# pic18f2550usbhdiio.net
KiCad netlist of a schematic drawn in EAGLE
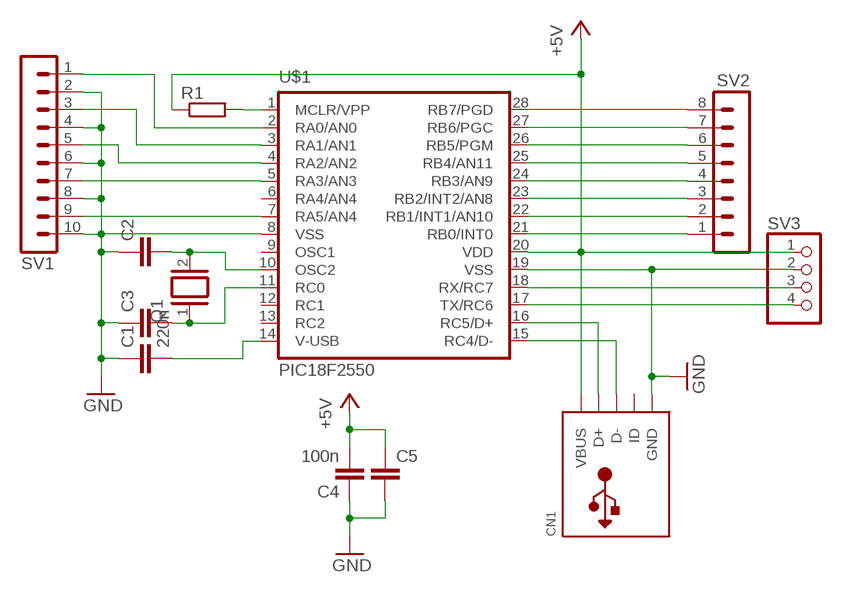
[diagram p0: schematic, sheet 1]

(export (version "E")
  (design (tool "Eeschema 10.0.6"))
  (components
    (comp (ref "C1")
      (value "220n")
      (footprint "eagle-import:C025-025X050")
      (libsource (lib "eagle-import") (part "C-EU025-025X050"))
    )
    (comp (ref "C2")
      (value "C-EU025-025X050")
      (footprint "eagle-import:C025-025X050")
      (libsource (lib "eagle-import") (part "C-EU025-025X050"))
    )
    (comp (ref "C3")
      (value "C-EU025-025X050")
      (footprint "eagle-import:C025-025X050")
      (libsource (lib "eagle-import") (part "C-EU025-025X050"))
    )
    (comp (ref "C4")
      (value "100n")
      (footprint "eagle-import:C025-025X050")
      (libsource (lib "eagle-import") (part "C-EU025-025X050"))
    )
    (comp (ref "C5")
      (value "C-EUC0805K")
      (footprint "eagle-import:C0805K")
      (libsource (lib "eagle-import") (part "C-EUC0805K"))
    )
    (comp (ref "CN1")
      (value "USBMOLEX")
      (footprint "eagle-import:USB-MINIB-THM-MOLEX")
      (libsource (lib "eagle-import") (part "USBMOLEX"))
    )
    (comp (ref "Q1")
      (value "XTAL/S")
      (footprint "eagle-import:QS")
      (libsource (lib "eagle-import") (part "XTAL/S"))
    )
    (comp (ref "R1")
      (value "R-EU_0207/10")
      (footprint "eagle-import:0207_10")
      (libsource (lib "eagle-import") (part "R-EU_0207/10"))
    )
    (comp (ref "SV1")
      (value "MA10-1")
      (footprint "eagle-import:MA10-1")
      (libsource (lib "eagle-import") (part "MA10-1"))
    )
    (comp (ref "SV2")
      (value "MA08-1")
      (footprint "eagle-import:MA08-1")
      (libsource (lib "eagle-import") (part "MA08-1"))
    )
    (comp (ref "SV3")
      (value "PINHD-1X4")
      (footprint "eagle-import:1X04")
      (libsource (lib "eagle-import") (part "PINHD-1X4"))
    )
    (comp (ref "U$1")
      (value "PIC18F2550")
      (footprint "eagle-import:DIL28-3")
      (libsource (lib "eagle-import") (part "PIC18F2550"))
    )
  )
  (nets
    (net (code "1") (name "+5V") (class "Default")
      (node (ref "C4") (pin "2") (pinfunction "2_2") (pintype "passive"))
      (node (ref "C5") (pin "1") (pinfunction "1_1") (pintype "passive"))
      (node (ref "CN1") (pin "VBUS") (pinfunction "VBUS_VBUS") (pintype "power_in"))
      (node (ref "R1") (pin "1") (pinfunction "1_1") (pintype "passive"))
      (node (ref "SV3") (pin "1") (pinfunction "1_1") (pintype "passive"))
      (node (ref "U$1") (pin "20") (pinfunction "VDD_20") (pintype "power_in"))
    )
    (net (code "2") (name "GND") (class "Default")
      (node (ref "C1") (pin "1") (pinfunction "1_1") (pintype "passive"))
      (node (ref "C2") (pin "1") (pinfunction "1_1") (pintype "passive"))
      (node (ref "C3") (pin "1") (pinfunction "1_1") (pintype "passive"))
      (node (ref "C4") (pin "1") (pinfunction "1_1") (pintype "passive"))
      (node (ref "C5") (pin "2") (pinfunction "2_2") (pintype "passive"))
      (node (ref "CN1") (pin "GND") (pinfunction "GND_GND") (pintype "power_in"))
      (node (ref "SV1") (pin "10") (pinfunction "10_10") (pintype "passive"))
      (node (ref "SV1") (pin "2") (pinfunction "2_2") (pintype "passive"))
      (node (ref "SV1") (pin "4") (pinfunction "4_4") (pintype "passive"))
      (node (ref "SV1") (pin "6") (pinfunction "6_6") (pintype "passive"))
      (node (ref "SV1") (pin "8") (pinfunction "8_8") (pintype "passive"))
      (node (ref "SV3") (pin "2") (pinfunction "2_2") (pintype "passive"))
      (node (ref "U$1") (pin "19") (pinfunction "VSS_19") (pintype "power_in"))
      (node (ref "U$1") (pin "8") (pinfunction "VSS_8") (pintype "power_in"))
    )
    (net (code "3") (name "Net-(U$1-MCLR{slash}VPP)") (class "Default")
      (node (ref "R1") (pin "2") (pinfunction "2_2") (pintype "passive"))
      (node (ref "U$1") (pin "1") (pinfunction "MCLR/VPP_1") (pintype "bidirectional"))
    )
    (net (code "4") (name "Net-(U$1-OSC2)") (class "Default")
      (node (ref "C2") (pin "2") (pinfunction "2_2") (pintype "passive"))
      (node (ref "Q1") (pin "2") (pinfunction "2_2") (pintype "passive"))
      (node (ref "U$1") (pin "10") (pinfunction "OSC2_10") (pintype "bidirectional"))
    )
    (net (code "5") (name "Net-(U$1-RA0{slash}AN0)") (class "Default")
      (node (ref "SV1") (pin "1") (pinfunction "1_1") (pintype "passive"))
      (node (ref "U$1") (pin "2") (pinfunction "RA0/AN0_2") (pintype "bidirectional"))
    )
    (net (code "6") (name "Net-(U$1-RA1{slash}AN1)") (class "Default")
      (node (ref "SV1") (pin "3") (pinfunction "3_3") (pintype "passive"))
      (node (ref "U$1") (pin "3") (pinfunction "RA1/AN1_3") (pintype "bidirectional"))
    )
    (net (code "7") (name "Net-(U$1-RA2{slash}AN2)") (class "Default")
      (node (ref "SV1") (pin "5") (pinfunction "5_5") (pintype "passive"))
      (node (ref "U$1") (pin "4") (pinfunction "RA2/AN2_4") (pintype "bidirectional"))
    )
    (net (code "8") (name "Net-(U$1-RA3{slash}AN3)") (class "Default")
      (node (ref "SV1") (pin "7") (pinfunction "7_7") (pintype "passive"))
      (node (ref "U$1") (pin "5") (pinfunction "RA3/AN3_5") (pintype "bidirectional"))
    )
    (net (code "9") (name "Net-(U$1-RA5{slash}AN4)") (class "Default")
      (node (ref "SV1") (pin "9") (pinfunction "9_9") (pintype "passive"))
      (node (ref "U$1") (pin "7") (pinfunction "RA5/AN4_7") (pintype "bidirectional"))
    )
    (net (code "10") (name "Net-(U$1-RB0{slash}INT0)") (class "Default")
      (node (ref "SV2") (pin "1") (pinfunction "1_1") (pintype "passive"))
      (node (ref "U$1") (pin "21") (pinfunction "RB0/INT0_21") (pintype "bidirectional"))
    )
    (net (code "11") (name "Net-(U$1-RB1{slash}INT1{slash}AN10)") (class "Default")
      (node (ref "SV2") (pin "2") (pinfunction "2_2") (pintype "passive"))
      (node (ref "U$1") (pin "22") (pinfunction "RB1/INT1/AN10_22") (pintype "bidirectional"))
    )
    (net (code "12") (name "Net-(U$1-RB2{slash}INT2{slash}AN8)") (class "Default")
      (node (ref "SV2") (pin "3") (pinfunction "3_3") (pintype "passive"))
      (node (ref "U$1") (pin "23") (pinfunction "RB2/INT2/AN8_23") (pintype "bidirectional"))
    )
    (net (code "13") (name "Net-(U$1-RB3{slash}AN9)") (class "Default")
      (node (ref "SV2") (pin "4") (pinfunction "4_4") (pintype "passive"))
      (node (ref "U$1") (pin "24") (pinfunction "RB3/AN9_24") (pintype "bidirectional"))
    )
    (net (code "14") (name "Net-(U$1-RB4{slash}AN11)") (class "Default")
      (node (ref "SV2") (pin "5") (pinfunction "5_5") (pintype "passive"))
      (node (ref "U$1") (pin "25") (pinfunction "RB4/AN11_25") (pintype "bidirectional"))
    )
    (net (code "15") (name "Net-(U$1-RB5{slash}PGM)") (class "Default")
      (node (ref "SV2") (pin "6") (pinfunction "6_6") (pintype "passive"))
      (node (ref "U$1") (pin "26") (pinfunction "RB5/PGM_26") (pintype "bidirectional"))
    )
    (net (code "16") (name "Net-(U$1-RB6{slash}PGC)") (class "Default")
      (node (ref "SV2") (pin "7") (pinfunction "7_7") (pintype "passive"))
      (node (ref "U$1") (pin "27") (pinfunction "RB6/PGC_27") (pintype "bidirectional"))
    )
    (net (code "17") (name "Net-(U$1-RB7{slash}PGD)") (class "Default")
      (node (ref "SV2") (pin "8") (pinfunction "8_8") (pintype "passive"))
      (node (ref "U$1") (pin "28") (pinfunction "RB7/PGD_28") (pintype "bidirectional"))
    )
    (net (code "18") (name "Net-(U$1-RC0)") (class "Default")
      (node (ref "C3") (pin "2") (pinfunction "2_2") (pintype "passive"))
      (node (ref "Q1") (pin "1") (pinfunction "1_1") (pintype "passive"))
      (node (ref "U$1") (pin "11") (pinfunction "RC0_11") (pintype "bidirectional"))
    )
    (net (code "19") (name "Net-(U$1-RC4{slash}D-)") (class "Default")
      (node (ref "CN1") (pin "D-") (pinfunction "D-_D-") (pintype "bidirectional"))
      (node (ref "U$1") (pin "15") (pinfunction "RC4/D-_15") (pintype "bidirectional"))
    )
    (net (code "20") (name "Net-(U$1-RC5{slash}D+)") (class "Default")
      (node (ref "CN1") (pin "D+") (pinfunction "D+_D+") (pintype "bidirectional"))
      (node (ref "U$1") (pin "16") (pinfunction "RC5/D+_16") (pintype "bidirectional"))
    )
    (net (code "21") (name "Net-(U$1-RX{slash}RC7)") (class "Default")
      (node (ref "SV3") (pin "3") (pinfunction "3_3") (pintype "passive"))
      (node (ref "U$1") (pin "18") (pinfunction "RX/RC7_18") (pintype "input"))
    )
    (net (code "22") (name "Net-(U$1-TX{slash}RC6)") (class "Default")
      (node (ref "SV3") (pin "4") (pinfunction "4_4") (pintype "passive"))
      (node (ref "U$1") (pin "17") (pinfunction "TX/RC6_17") (pintype "bidirectional"))
    )
    (net (code "23") (name "Net-(U$1-V-USB)") (class "Default")
      (node (ref "C1") (pin "2") (pinfunction "2_2") (pintype "passive"))
      (node (ref "U$1") (pin "14") (pinfunction "V-USB_14") (pintype "bidirectional"))
    )
    (net (code "24") (name "unconnected-(CN1-PadID)") (class "Default")
      (node (ref "CN1") (pin "ID") (pinfunction "ID_ID") (pintype "bidirectional"))
    )
    (net (code "25") (name "unconnected-(U$1-OSC1-Pad9)") (class "Default")
      (node (ref "U$1") (pin "9") (pinfunction "OSC1_9") (pintype "bidirectional"))
    )
    (net (code "26") (name "unconnected-(U$1-RA4{slash}AN4-Pad6)") (class "Default")
      (node (ref "U$1") (pin "6") (pinfunction "RA4/AN4_6") (pintype "bidirectional"))
    )
    (net (code "27") (name "unconnected-(U$1-RC1-Pad12)") (class "Default")
      (node (ref "U$1") (pin "12") (pinfunction "RC1_12") (pintype "bidirectional"))
    )
    (net (code "28") (name "unconnected-(U$1-RC2-Pad13)") (class "Default")
      (node (ref "U$1") (pin "13") (pinfunction "RC2_13") (pintype "bidirectional"))
    )
  )
)
